# 3V_Switch.net
KiCad netlist of a schematic drawn in Altium Designer
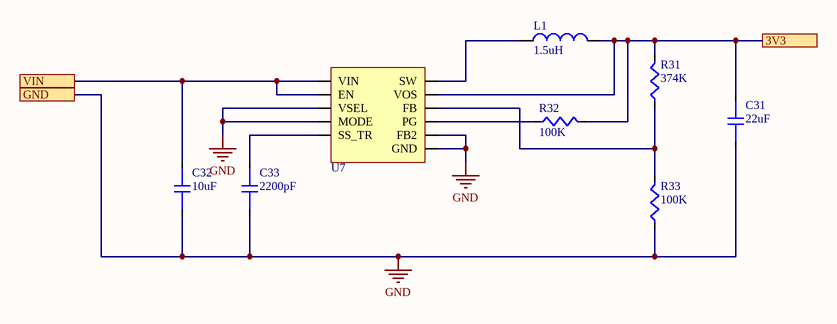
[diagram p0: 3V_Switch.SchDoc]

(export (version "E")
  (design (tool "Eeschema 10.0.6"))
  (components
    (comp (ref "C31")
      (value "22uF")
      (description "CAP CER 22UF 6.3V X7T 0805")
      (fields (field (name "TOLERANCE") "20%"))
      (libsource (lib "SwitchingSupply") (part "GRM21BD70J226ME44L"))
    )
    (comp (ref "C32")
      (value "10uF")
      (description "CAP CER 10UF 25V X7R 1206")
      (fields (field (name "TOLERANCE") "20%"))
      (libsource (lib "SwitchingSupply") (part "GRM31CR71E106KA12L"))
    )
    (comp (ref "C33")
      (value "2200pF")
      (description "CAP CER 2200PF 25V X7R 0402")
      (fields (field (name "TOLERANCE") "20%"))
      (libsource (lib "SwitchingSupply") (part "GRM155R71E222KA01D"))
    )
    (comp (ref "L1")
      (value "1.5uH")
      (description "FIXED IND 1.5UH 7.2A 20.7 MOHM")
      (fields (field (name "TOLERANCE") "20%"))
      (libsource (lib "SwitchingSupply") (part "IHLP2020CZER1R5M01"))
    )
    (comp (ref "R31")
      (value "374K")
      (description "RES SMD 374K OHM 1% 1/16W 0402")
      (fields (field (name "TOLERANCE") "20%"))
      (libsource (lib "SwitchingSupply") (part "CRCW0402374KFKED"))
    )
    (comp (ref "R32")
      (value "100K")
      (description "RES SMD 100K OHM 1% 1/16W 0402")
      (fields (field (name "TOLERANCE") "20%"))
      (libsource (lib "SwitchingSupply") (part "CRCW0402100KFKED"))
    )
    (comp (ref "R33")
      (value "100K")
      (description "RES SMD 100K OHM 1% 1/16W 0402")
      (fields (field (name "TOLERANCE") "20%"))
      (libsource (lib "SwitchingSupply") (part "CRCW0402100KFKED"))
    )
    (comp (ref "U7")
      (value "TPS621361RGXR")
      (description "3-17V 4.0A Step-Down Converter with 1% accuracy and PFM/Forced-PWM in 2x3QFN")
      (libsource (lib "SwitchingSupply") (part "TPS621361RGXR"))
    )
  )
  (nets
    (net (code "1") (name "/3V3") (class "Default")
      (node (ref "C31") (pin "2") (pinfunction "2_2") (pintype "passive"))
      (node (ref "L1") (pin "2") (pinfunction "2_2") (pintype "passive"))
      (node (ref "R31") (pin "1") (pinfunction "1_1") (pintype "passive"))
      (node (ref "R32") (pin "1") (pinfunction "1_1") (pintype "passive"))
      (node (ref "U7") (pin "6") (pinfunction "VOS_6") (pintype "passive"))
    )
    (net (code "2") (name "/VIN") (class "Default")
      (node (ref "C32") (pin "2") (pinfunction "2_2") (pintype "passive"))
      (node (ref "U7") (pin "1") (pinfunction "VIN_1") (pintype "passive"))
      (node (ref "U7") (pin "8") (pinfunction "EN_8") (pintype "passive"))
    )
    (net (code "3") (name "GND") (class "Default")
      (node (ref "C31") (pin "1") (pinfunction "1_1") (pintype "passive"))
      (node (ref "C32") (pin "1") (pinfunction "1_1") (pintype "passive"))
      (node (ref "C33") (pin "1") (pinfunction "1_1") (pintype "passive"))
      (node (ref "R33") (pin "2") (pinfunction "2_2") (pintype "passive"))
      (node (ref "U7") (pin "10") (pinfunction "MODE_10") (pintype "passive"))
      (node (ref "U7") (pin "11") (pinfunction "VSEL_11") (pintype "passive"))
      (node (ref "U7") (pin "3") (pinfunction "GND_3") (pintype "passive"))
      (node (ref "U7") (pin "4") (pinfunction "FB2_4") (pintype "passive"))
    )
    (net (code "4") (name "Net-(U7-FB)") (class "Default")
      (node (ref "R31") (pin "2") (pinfunction "2_2") (pintype "passive"))
      (node (ref "R33") (pin "1") (pinfunction "1_1") (pintype "passive"))
      (node (ref "U7") (pin "5") (pinfunction "FB_5") (pintype "passive"))
    )
    (net (code "5") (name "Net-(U7-PG)") (class "Default")
      (node (ref "R32") (pin "2") (pinfunction "2_2") (pintype "passive"))
      (node (ref "U7") (pin "7") (pinfunction "PG_7") (pintype "passive"))
    )
    (net (code "6") (name "Net-(U7-SS_TR)") (class "Default")
      (node (ref "C33") (pin "2") (pinfunction "2_2") (pintype "passive"))
      (node (ref "U7") (pin "9") (pinfunction "SS_TR_9") (pintype "passive"))
    )
    (net (code "7") (name "Net-(U7-SW)") (class "Default")
      (node (ref "L1") (pin "1") (pinfunction "1_1") (pintype "passive"))
      (node (ref "U7") (pin "2") (pinfunction "SW_2") (pintype "passive"))
    )
  )
)
